# spb_sch1.net
KiCad netlist of a schematic drawn in Altium Designer
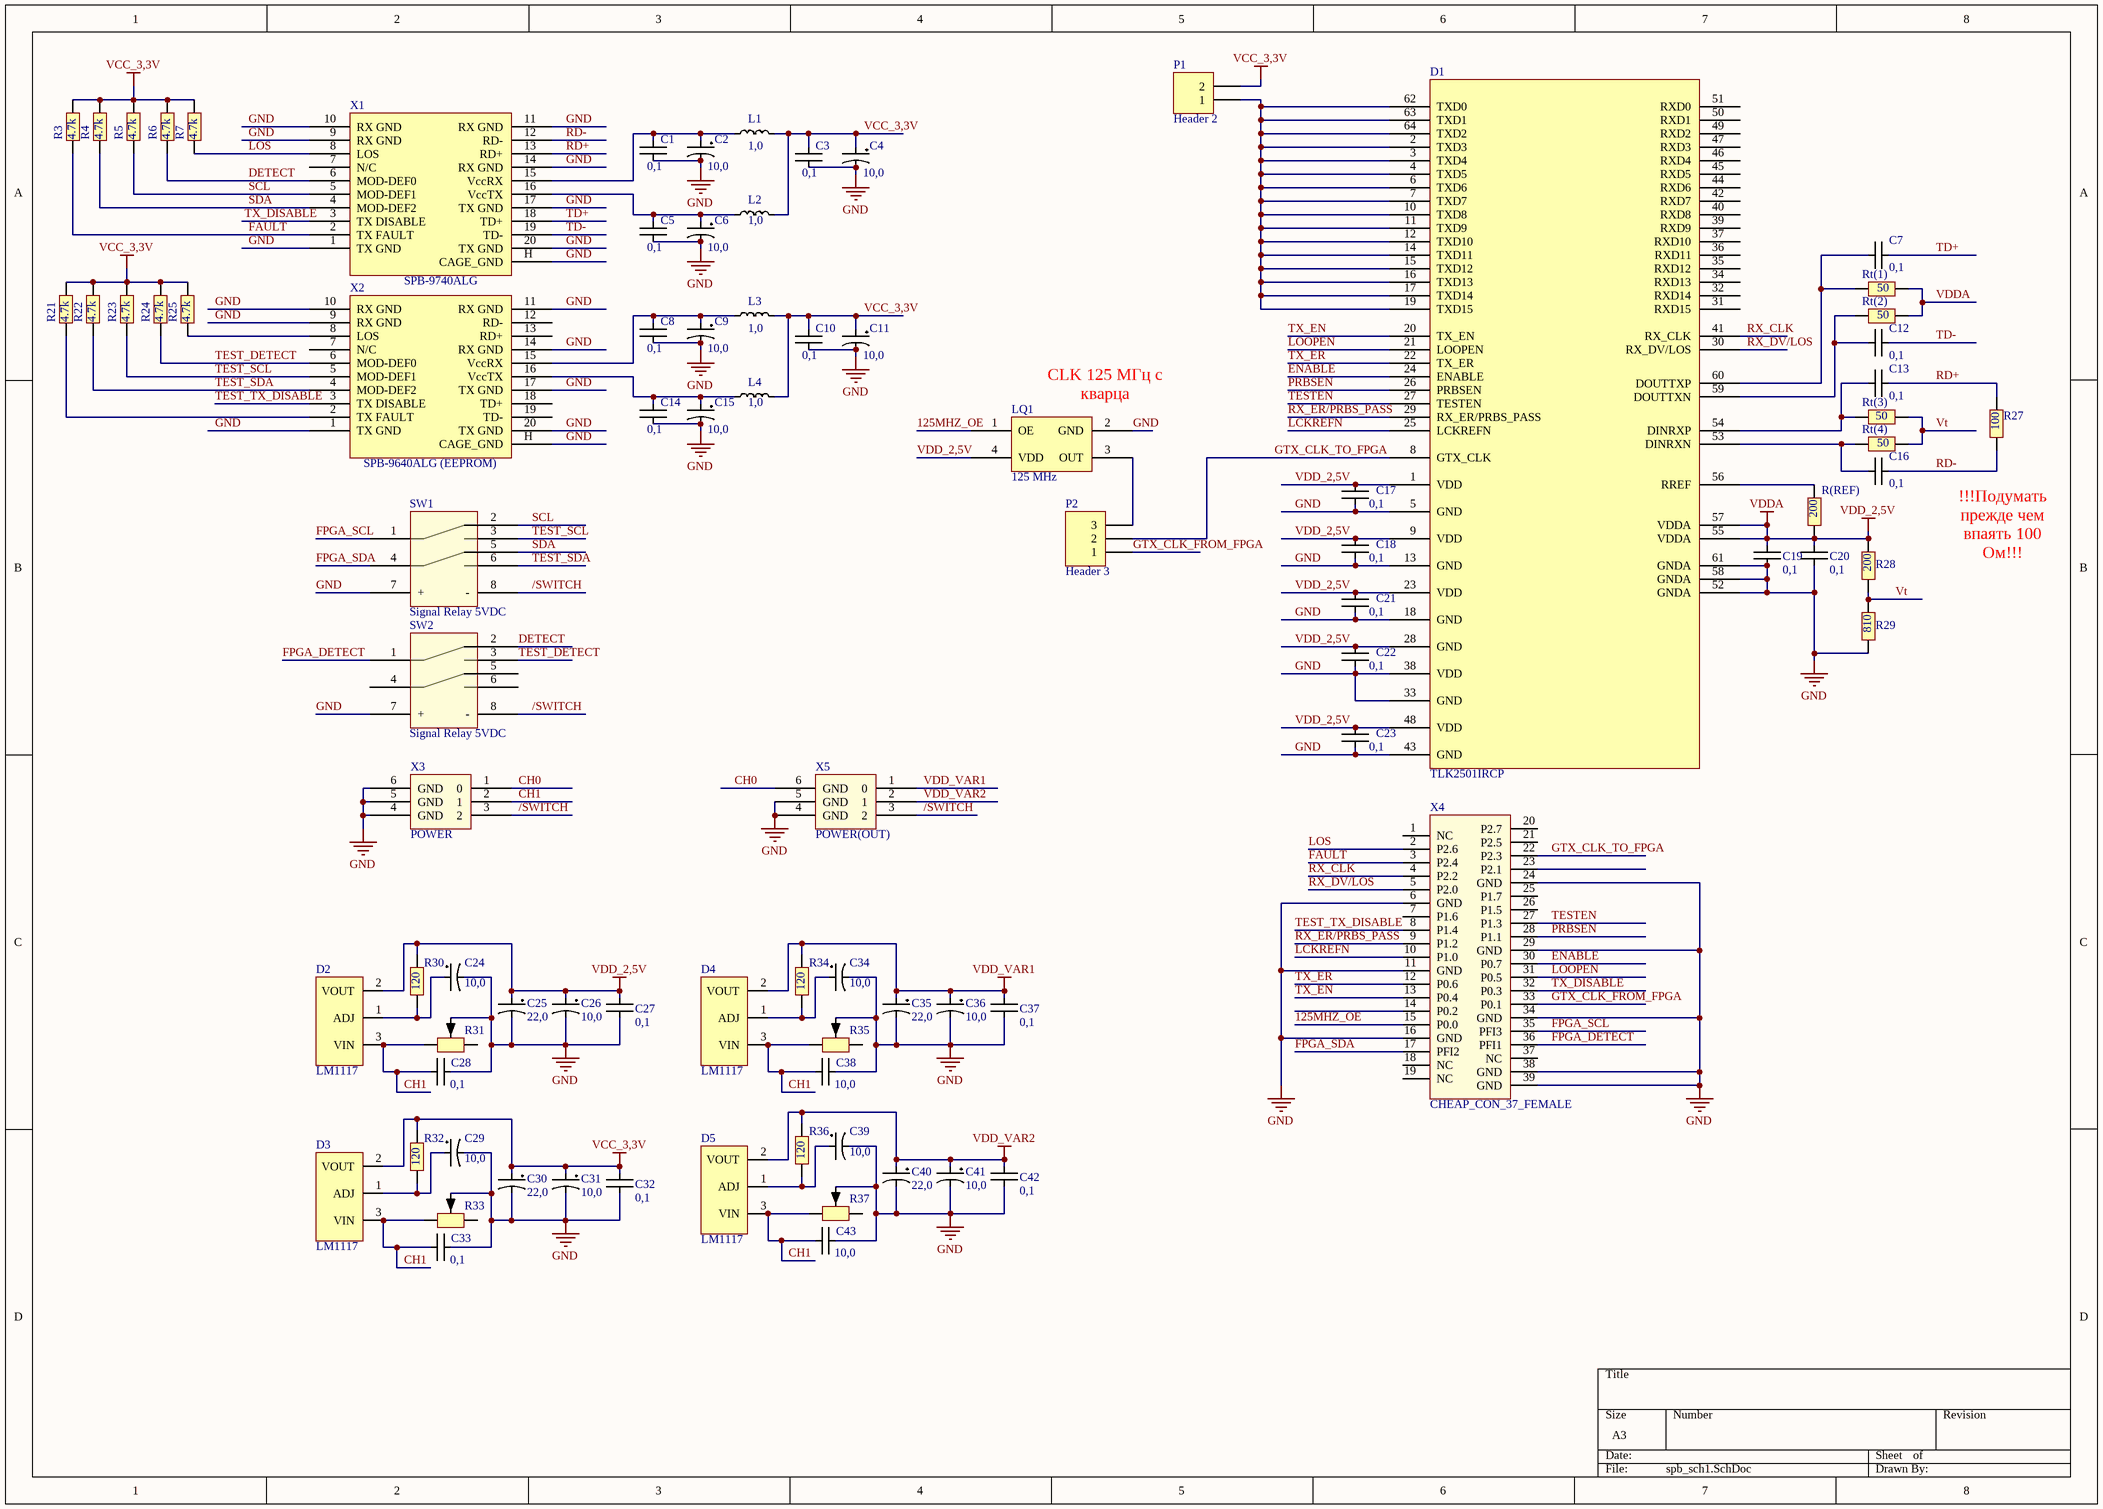
[diagram p0: spb_sch1.SchDoc]

(export (version "E")
  (design (tool "Eeschema 10.0.6"))
  (components
    (comp (ref "C1")
      (value "0,1")
      (footprint "0805")
      (description "0805")
      (libsource (lib "MIT_Schlib") (part "CAP_SMALL"))
    )
    (comp (ref "C2")
      (value "10,0")
      (footprint "TYPE_C")
      (description "SMD")
      (libsource (lib "MIT_Schlib") (part "CAP_TANT"))
    )
    (comp (ref "C3")
      (value "0,1")
      (footprint "0805")
      (description "0805")
      (libsource (lib "MIT_Schlib") (part "CAP_SMALL"))
    )
    (comp (ref "C4")
      (value "10,0")
      (footprint "TYPE_C")
      (description "SMD")
      (libsource (lib "MIT_Schlib") (part "CAP_TANT"))
    )
    (comp (ref "C5")
      (value "0,1")
      (footprint "0805")
      (description "0805")
      (libsource (lib "MIT_Schlib") (part "CAP_SMALL"))
    )
    (comp (ref "C6")
      (value "10,0")
      (footprint "TYPE_C")
      (description "SMD")
      (libsource (lib "MIT_Schlib") (part "CAP_TANT"))
    )
    (comp (ref "C7")
      (value "0,1")
      (footprint "0805")
      (description "0805")
      (libsource (lib "MIT_Schlib") (part "CAP_SMALL"))
    )
    (comp (ref "C8")
      (value "0,1")
      (footprint "0805")
      (description "0805")
      (libsource (lib "MIT_Schlib") (part "CAP_SMALL"))
    )
    (comp (ref "C9")
      (value "10,0")
      (footprint "TYPE_C")
      (description "SMD")
      (libsource (lib "MIT_Schlib") (part "CAP_TANT"))
    )
    (comp (ref "C10")
      (value "0,1")
      (footprint "0805")
      (description "0805")
      (libsource (lib "MIT_Schlib") (part "CAP_SMALL"))
    )
    (comp (ref "C11")
      (value "10,0")
      (footprint "TYPE_C")
      (description "SMD")
      (libsource (lib "MIT_Schlib") (part "CAP_TANT"))
    )
    (comp (ref "C12")
      (value "0,1")
      (footprint "0805")
      (description "0805")
      (libsource (lib "MIT_Schlib") (part "CAP_SMALL"))
    )
    (comp (ref "C13")
      (value "0,1")
      (footprint "0805")
      (description "0805")
      (libsource (lib "MIT_Schlib") (part "CAP_SMALL"))
    )
    (comp (ref "C14")
      (value "0,1")
      (footprint "0805")
      (description "0805")
      (libsource (lib "MIT_Schlib") (part "CAP_SMALL"))
    )
    (comp (ref "C15")
      (value "10,0")
      (footprint "TYPE_C")
      (description "SMD")
      (libsource (lib "MIT_Schlib") (part "CAP_TANT"))
    )
    (comp (ref "C16")
      (value "0,1")
      (footprint "0805")
      (description "0805")
      (libsource (lib "MIT_Schlib") (part "CAP_SMALL"))
    )
    (comp (ref "C17")
      (value "0,1")
      (footprint "0805")
      (description "0805")
      (libsource (lib "MIT_Schlib") (part "CAP_SMALL"))
    )
    (comp (ref "C18")
      (value "0,1")
      (footprint "0805")
      (description "0805")
      (libsource (lib "MIT_Schlib") (part "CAP_SMALL"))
    )
    (comp (ref "C19")
      (value "0,1")
      (footprint "0805")
      (description "0805")
      (libsource (lib "MIT_Schlib") (part "CAP_SMALL"))
    )
    (comp (ref "C20")
      (value "0,1")
      (footprint "0805")
      (description "0805")
      (libsource (lib "MIT_Schlib") (part "CAP_SMALL"))
    )
    (comp (ref "C21")
      (value "0,1")
      (footprint "0805")
      (description "0805")
      (libsource (lib "MIT_Schlib") (part "CAP_SMALL"))
    )
    (comp (ref "C22")
      (value "0,1")
      (footprint "0805")
      (description "0805")
      (libsource (lib "MIT_Schlib") (part "CAP_SMALL"))
    )
    (comp (ref "C23")
      (value "0,1")
      (footprint "0805")
      (description "0805")
      (libsource (lib "MIT_Schlib") (part "CAP_SMALL"))
    )
    (comp (ref "C24")
      (value "10,0")
      (footprint "TYPE_C")
      (description "SMD")
      (libsource (lib "MIT_Schlib") (part "CAP_TANT"))
    )
    (comp (ref "C25")
      (value "22,0")
      (footprint "TYPE_C")
      (description "SMD")
      (libsource (lib "MIT_Schlib") (part "CAP_TANT"))
    )
    (comp (ref "C26")
      (value "10,0")
      (footprint "TYPE_C")
      (description "SMD")
      (libsource (lib "MIT_Schlib") (part "CAP_TANT"))
    )
    (comp (ref "C27")
      (value "0,1")
      (footprint "0805")
      (description "0805")
      (libsource (lib "MIT_Schlib") (part "CAP_SMALL"))
    )
    (comp (ref "C28")
      (value "0,1")
      (footprint "0805")
      (description "0805")
      (libsource (lib "MIT_Schlib") (part "CAP_SMALL"))
    )
    (comp (ref "C29")
      (value "10,0")
      (footprint "TYPE_C")
      (description "SMD")
      (libsource (lib "MIT_Schlib") (part "CAP_TANT"))
    )
    (comp (ref "C30")
      (value "22,0")
      (footprint "TYPE_C")
      (description "SMD")
      (libsource (lib "MIT_Schlib") (part "CAP_TANT"))
    )
    (comp (ref "C31")
      (value "10,0")
      (footprint "TYPE_C")
      (description "SMD")
      (libsource (lib "MIT_Schlib") (part "CAP_TANT"))
    )
    (comp (ref "C32")
      (value "0,1")
      (footprint "0805")
      (description "0805")
      (libsource (lib "MIT_Schlib") (part "CAP_SMALL"))
    )
    (comp (ref "C33")
      (value "0,1")
      (footprint "0805")
      (description "0805")
      (libsource (lib "MIT_Schlib") (part "CAP_SMALL"))
    )
    (comp (ref "C34")
      (value "10,0")
      (footprint "TYPE_C")
      (description "SMD")
      (libsource (lib "MIT_Schlib") (part "CAP_TANT"))
    )
    (comp (ref "C35")
      (value "22,0")
      (footprint "TYPE_C")
      (description "SMD")
      (libsource (lib "MIT_Schlib") (part "CAP_TANT"))
    )
    (comp (ref "C36")
      (value "10,0")
      (footprint "TYPE_C")
      (description "SMD")
      (libsource (lib "MIT_Schlib") (part "CAP_TANT"))
    )
    (comp (ref "C37")
      (value "0,1")
      (footprint "0805")
      (description "0805")
      (libsource (lib "MIT_Schlib") (part "CAP_SMALL"))
    )
    (comp (ref "C38")
      (value "10,0")
      (footprint "0805")
      (description "0805")
      (libsource (lib "MIT_Schlib") (part "CAP_SMALL"))
    )
    (comp (ref "C39")
      (value "10,0")
      (footprint "TYPE_C")
      (description "SMD")
      (libsource (lib "MIT_Schlib") (part "CAP_TANT"))
    )
    (comp (ref "C40")
      (value "22,0")
      (footprint "TYPE_C")
      (description "SMD")
      (libsource (lib "MIT_Schlib") (part "CAP_TANT"))
    )
    (comp (ref "C41")
      (value "10,0")
      (footprint "TYPE_C")
      (description "SMD")
      (libsource (lib "MIT_Schlib") (part "CAP_TANT"))
    )
    (comp (ref "C42")
      (value "0,1")
      (footprint "0805")
      (description "0805")
      (libsource (lib "MIT_Schlib") (part "CAP_SMALL"))
    )
    (comp (ref "C43")
      (value "10,0")
      (footprint "0805")
      (description "0805")
      (libsource (lib "MIT_Schlib") (part "CAP_SMALL"))
    )
    (comp (ref "D1")
      (value "TLK2501IRCP")
      (footprint "Quad64")
      (libsource (lib "MIT_Schlib") (part "TLK2501IRCP"))
    )
    (comp (ref "D2") (value "LM1117") (footprint "TO-252") (libsource (lib "MIT_Schlib") (part "LM1117_ADJ")))
    (comp (ref "D3") (value "LM1117") (footprint "TO-252") (libsource (lib "MIT_Schlib") (part "LM1117_ADJ")))
    (comp (ref "D4") (value "LM1117") (footprint "TO-252") (libsource (lib "MIT_Schlib") (part "LM1117_ADJ")))
    (comp (ref "D5") (value "LM1117") (footprint "TO-252") (libsource (lib "MIT_Schlib") (part "LM1117_ADJ")))
    (comp (ref "L1")
      (value "1,0")
      (footprint "0805")
      (description "0805")
      (libsource (lib "MIT_Schlib") (part "INDUCT"))
    )
    (comp (ref "L2")
      (value "1,0")
      (footprint "0805")
      (description "0805")
      (libsource (lib "MIT_Schlib") (part "INDUCT"))
    )
    (comp (ref "L3")
      (value "1,0")
      (footprint "0805")
      (description "0805")
      (libsource (lib "MIT_Schlib") (part "INDUCT"))
    )
    (comp (ref "L4")
      (value "1,0")
      (footprint "0805")
      (description "0805")
      (libsource (lib "MIT_Schlib") (part "INDUCT"))
    )
    (comp (ref "LQ1")
      (value "125 MHz")
      (footprint "SOC7 SMD Clock Oscillator")
      (libsource (lib "MIT_Schlib") (part "SOC7 SMD Clock Oscillator"))
    )
    (comp (ref "P1")
      (value "Header 2")
      (footprint "HDR1X2")
      (description "Header, 2-Pin")
      (fields (field (name "PUBLISHER") "Altium Limited"))
      (libsource (lib "Miscellaneous Connectors") (part "Header 2"))
    )
    (comp (ref "P2")
      (value "Header 3")
      (footprint "HDR1X3")
      (description "Header, 3-Pin")
      (fields (field (name "PUBLISHER") "Altium Limited"))
      (libsource (lib "Miscellaneous Connectors") (part "Header 3"))
    )
    (comp (ref "R(REF)")
      (value "200")
      (footprint "0805")
      (description "0805")
      (libsource (lib "") (part "RES0805_1"))
    )
    (comp (ref "R3")
      (value "4.7k")
      (footprint "0805")
      (description "0805")
      (libsource (lib "") (part "RES0805_2"))
    )
    (comp (ref "R4")
      (value "4.7k")
      (footprint "0805")
      (description "0805")
      (libsource (lib "") (part "RES0805_2"))
    )
    (comp (ref "R5")
      (value "4.7k")
      (footprint "0805")
      (description "0805")
      (libsource (lib "") (part "RES0805_2"))
    )
    (comp (ref "R6")
      (value "4.7k")
      (footprint "0805")
      (description "0805")
      (libsource (lib "") (part "RES0805_2"))
    )
    (comp (ref "R7")
      (value "4.7k")
      (footprint "0805")
      (description "0805")
      (libsource (lib "") (part "RES0805_2"))
    )
    (comp (ref "R21")
      (value "4.7k")
      (footprint "0805")
      (description "0805")
      (libsource (lib "") (part "RES0805_2"))
    )
    (comp (ref "R22")
      (value "4.7k")
      (footprint "0805")
      (description "0805")
      (libsource (lib "") (part "RES0805_2"))
    )
    (comp (ref "R23")
      (value "4.7k")
      (footprint "0805")
      (description "0805")
      (libsource (lib "") (part "RES0805_2"))
    )
    (comp (ref "R24")
      (value "4.7k")
      (footprint "0805")
      (description "0805")
      (libsource (lib "") (part "RES0805_2"))
    )
    (comp (ref "R25")
      (value "4.7k")
      (footprint "0805")
      (description "0805")
      (libsource (lib "") (part "RES0805_2"))
    )
    (comp (ref "R27")
      (value "100")
      (footprint "0805")
      (description "0805")
      (libsource (lib "") (part "RES0805_2"))
    )
    (comp (ref "R28")
      (value "200")
      (footprint "0805")
      (description "0805")
      (libsource (lib "") (part "RES0805_1"))
    )
    (comp (ref "R29")
      (value "810")
      (footprint "0805")
      (description "0805")
      (libsource (lib "") (part "RES0805_1"))
    )
    (comp (ref "R30")
      (value "120")
      (footprint "0805")
      (description "0805")
      (libsource (lib "") (part "RES0805_2"))
    )
    (comp (ref "R31")
      (value "RES_VAR")
      (footprint "3006P")
      (description "PV36W102C (СП5-2ВБ) 1 кОм")
      (libsource (lib "MIT_Schlib") (part "RES_VAR"))
    )
    (comp (ref "R32") (value "120") (footprint "0805") (libsource (lib "") (part "RES0805_2")))
    (comp (ref "R33")
      (value "RES_VAR")
      (footprint "3006P")
      (description "PV36W102C (СП5-2ВБ) 1 кОм")
      (libsource (lib "MIT_Schlib") (part "RES_VAR"))
    )
    (comp (ref "R34")
      (value "120")
      (footprint "0805")
      (description "0805")
      (libsource (lib "") (part "RES0805_2"))
    )
    (comp (ref "R35")
      (value "RES_VAR")
      (footprint "3006P")
      (description "PV36W102C (СП5-2ВБ) 1 кОм")
      (libsource (lib "MIT_Schlib") (part "RES_VAR"))
    )
    (comp (ref "R36")
      (value "120")
      (footprint "0805")
      (description "0805")
      (libsource (lib "") (part "RES0805_2"))
    )
    (comp (ref "R37")
      (value "RES_VAR")
      (footprint "3006P")
      (description "PV36W102C (СП5-2ВБ) 1 кОм")
      (libsource (lib "MIT_Schlib") (part "RES_VAR"))
    )
    (comp (ref "Rt(1)")
      (value "50")
      (footprint "0805")
      (description "0805")
      (libsource (lib "MIT_Schlib") (part "RES0805"))
    )
    (comp (ref "Rt(2)")
      (value "50")
      (footprint "0805")
      (description "0805")
      (libsource (lib "MIT_Schlib") (part "RES0805"))
    )
    (comp (ref "Rt(3)")
      (value "50")
      (footprint "0805")
      (description "0805")
      (libsource (lib "MIT_Schlib") (part "RES0805"))
    )
    (comp (ref "Rt(4)")
      (value "50")
      (footprint "0805")
      (description "0805")
      (libsource (lib "MIT_Schlib") (part "RES0805"))
    )
    (comp (ref "SW1")
      (value "Signal Relay 5VDC")
      (footprint "V23079 Relay")
      (libsource (lib "MIT_Schlib") (part "SWITCH"))
    )
    (comp (ref "SW2")
      (value "Signal Relay 5VDC")
      (footprint "V23079 Relay")
      (libsource (lib "MIT_Schlib") (part "SWITCH"))
    )
    (comp (ref "X1")
      (value "SPB-9740ALG")
      (footprint "SFP-20pin")
      (libsource (lib "MIT_Schlib") (part "SFP-20pin"))
    )
    (comp (ref "X2")
      (value "SPB-9640ALG (EEPROM)")
      (footprint "SFP-20pin")
      (libsource (lib "MIT_Schlib") (part "SFP-20pin"))
    )
    (comp (ref "X3") (value "POWER") (footprint "POWER") (libsource (lib "Schlib") (part "POWER")))
    (comp (ref "X4")
      (value "CHEAP_CON_37_FEMALE")
      (footprint "CHEAP_CONN_FEMALE")
      (libsource (lib "Schlib") (part "CHEAP_CON_37_FEMALE"))
    )
    (comp (ref "X5") (value "POWER(OUT)") (footprint "POWER") (libsource (lib "Schlib") (part "POWER")))
  )
  (nets
    (net (code "1") (name "/125MHZ_OE") (class "Default")
      (node (ref "LQ1") (pin "1") (pinfunction "OE_1") (pintype "passive"))
      (node (ref "X4") (pin "15") (pinfunction "P0.0_15") (pintype "passive"))
    )
    (net (code "3") (name "/CH0") (class "Default")
      (node (ref "X3") (pin "1") (pinfunction "0_1") (pintype "passive"))
      (node (ref "X5") (pin "6") (pinfunction "GND_6") (pintype "passive"))
    )
    (net (code "4") (name "/CH1") (class "Default")
      (node (ref "C28") (pin "1") (pinfunction "1_1") (pintype "passive"))
      (node (ref "C33") (pin "1") (pinfunction "1_1") (pintype "passive"))
      (node (ref "C38") (pin "1") (pinfunction "1_1") (pintype "passive"))
      (node (ref "C43") (pin "1") (pinfunction "1_1") (pintype "passive"))
      (node (ref "D2") (pin "3") (pinfunction "VIN_3") (pintype "passive"))
      (node (ref "D3") (pin "3") (pinfunction "VIN_3") (pintype "passive"))
      (node (ref "D4") (pin "3") (pinfunction "VIN_3") (pintype "passive"))
      (node (ref "D5") (pin "3") (pinfunction "VIN_3") (pintype "passive"))
      (node (ref "R31") (pin "3") (pinfunction "3_3") (pintype "passive"))
      (node (ref "R33") (pin "3") (pinfunction "3_3") (pintype "passive"))
      (node (ref "R35") (pin "3") (pinfunction "3_3") (pintype "passive"))
      (node (ref "R37") (pin "3") (pinfunction "3_3") (pintype "passive"))
      (node (ref "X3") (pin "2") (pinfunction "1_2") (pintype "passive"))
    )
    (net (code "5") (name "/DETECT") (class "Default")
      (node (ref "R6") (pin "2") (pinfunction "2_2") (pintype "passive"))
      (node (ref "SW2") (pin "2") (pinfunction "-_2") (pintype "passive"))
      (node (ref "X1") (pin "6") (pinfunction "MOD-DEF0_6") (pintype "passive"))
    )
    (net (code "6") (name "/ENABLE") (class "Default")
      (node (ref "D1") (pin "24") (pinfunction "ENABLE_24") (pintype "passive"))
      (node (ref "X4") (pin "30") (pinfunction "P0.7_30") (pintype "passive"))
    )
    (net (code "7") (name "/FAULT") (class "Default")
      (node (ref "R3") (pin "2") (pinfunction "2_2") (pintype "passive"))
      (node (ref "X1") (pin "2") (pinfunction "TX_FAULT_2") (pintype "passive"))
      (node (ref "X4") (pin "3") (pinfunction "P2.4_3") (pintype "passive"))
    )
    (net (code "8") (name "/FPGA_DETECT") (class "Default")
      (node (ref "SW2") (pin "1") (pinfunction "-_1") (pintype "passive"))
      (node (ref "X4") (pin "36") (pinfunction "PFI1_36") (pintype "passive"))
    )
    (net (code "9") (name "/FPGA_SCL") (class "Default")
      (node (ref "SW1") (pin "1") (pinfunction "-_1") (pintype "passive"))
      (node (ref "X4") (pin "35") (pinfunction "PFI3_35") (pintype "passive"))
    )
    (net (code "10") (name "/FPGA_SDA") (class "Default")
      (node (ref "SW1") (pin "4") (pinfunction "-_4") (pintype "passive"))
      (node (ref "X4") (pin "17") (pinfunction "PFI2_17") (pintype "passive"))
    )
    (net (code "11") (name "/GTX_CLK_FROM_FPGA") (class "Default")
      (node (ref "P2") (pin "1") (pinfunction "1_1") (pintype "passive"))
      (node (ref "X4") (pin "33") (pinfunction "P0.1_33") (pintype "passive"))
    )
    (net (code "12") (name "/GTX_CLK_TO_FPGA") (class "Default")
      (node (ref "D1") (pin "8") (pinfunction "GTX_CLK_8") (pintype "passive"))
      (node (ref "P2") (pin "2") (pinfunction "2_2") (pintype "passive"))
      (node (ref "X4") (pin "22") (pinfunction "P2.3_22") (pintype "passive"))
    )
    (net (code "13") (name "/LCKREFN") (class "Default")
      (node (ref "D1") (pin "25") (pinfunction "LCKREFN_25") (pintype "passive"))
      (node (ref "X4") (pin "10") (pinfunction "P1.0_10") (pintype "passive"))
    )
    (net (code "14") (name "/LOOPEN") (class "Default")
      (node (ref "D1") (pin "21") (pinfunction "LOOPEN_21") (pintype "passive"))
      (node (ref "X4") (pin "31") (pinfunction "P0.5_31") (pintype "passive"))
    )
    (net (code "15") (name "/LOS") (class "Default")
      (node (ref "R7") (pin "2") (pinfunction "2_2") (pintype "passive"))
      (node (ref "X1") (pin "8") (pinfunction "LOS_8") (pintype "passive"))
      (node (ref "X4") (pin "2") (pinfunction "P2.6_2") (pintype "passive"))
    )
    (net (code "16") (name "/PRBSEN") (class "Default")
      (node (ref "D1") (pin "26") (pinfunction "PRBSEN_26") (pintype "passive"))
      (node (ref "X4") (pin "28") (pinfunction "P1.1_28") (pintype "passive"))
    )
    (net (code "17") (name "/RD+") (class "Default")
      (node (ref "C13") (pin "1") (pinfunction "1_1") (pintype "passive"))
      (node (ref "R27") (pin "1") (pinfunction "1_1") (pintype "passive"))
      (node (ref "X1") (pin "13") (pinfunction "RD+_13") (pintype "passive"))
    )
    (net (code "18") (name "/RD-") (class "Default")
      (node (ref "C16") (pin "1") (pinfunction "1_1") (pintype "passive"))
      (node (ref "R27") (pin "2") (pinfunction "2_2") (pintype "passive"))
      (node (ref "X1") (pin "12") (pinfunction "RD-_12") (pintype "passive"))
    )
    (net (code "19") (name "/RX_CLK") (class "Default")
      (node (ref "D1") (pin "41") (pinfunction "RX_CLK_41") (pintype "passive"))
      (node (ref "X4") (pin "4") (pinfunction "P2.2_4") (pintype "passive"))
    )
    (net (code "20") (name "/RX_DV{slash}LOS") (class "Default")
      (node (ref "D1") (pin "30") (pinfunction "RX_DV/LOS_30") (pintype "passive"))
      (node (ref "X4") (pin "5") (pinfunction "P2.0_5") (pintype "passive"))
    )
    (net (code "21") (name "/RX_ER{slash}PRBS_PASS") (class "Default")
      (node (ref "D1") (pin "29") (pinfunction "RX_ER/PRBS_PASS_29") (pintype "passive"))
      (node (ref "X4") (pin "9") (pinfunction "P1.2_9") (pintype "passive"))
    )
    (net (code "22") (name "/SCL") (class "Default")
      (node (ref "R5") (pin "2") (pinfunction "2_2") (pintype "passive"))
      (node (ref "SW1") (pin "2") (pinfunction "-_2") (pintype "passive"))
      (node (ref "X1") (pin "5") (pinfunction "MOD-DEF1_5") (pintype "passive"))
    )
    (net (code "23") (name "/SDA") (class "Default")
      (node (ref "R4") (pin "2") (pinfunction "2_2") (pintype "passive"))
      (node (ref "SW1") (pin "5") (pinfunction "-_5") (pintype "passive"))
      (node (ref "X1") (pin "4") (pinfunction "MOD-DEF2_4") (pintype "passive"))
    )
    (net (code "24") (name "/TD+") (class "Default")
      (node (ref "C7") (pin "1") (pinfunction "1_1") (pintype "passive"))
      (node (ref "X1") (pin "18") (pinfunction "TD+_18") (pintype "passive"))
    )
    (net (code "25") (name "/TD-") (class "Default")
      (node (ref "C12") (pin "1") (pinfunction "1_1") (pintype "passive"))
      (node (ref "X1") (pin "19") (pinfunction "TD-_19") (pintype "passive"))
    )
    (net (code "26") (name "/TESTEN") (class "Default")
      (node (ref "D1") (pin "27") (pinfunction "TESTEN_27") (pintype "passive"))
      (node (ref "X4") (pin "27") (pinfunction "P1.3_27") (pintype "passive"))
    )
    (net (code "27") (name "/TEST_DETECT") (class "Default")
      (node (ref "R24") (pin "2") (pinfunction "2_2") (pintype "passive"))
      (node (ref "SW2") (pin "3") (pinfunction "-_3") (pintype "passive"))
      (node (ref "X2") (pin "6") (pinfunction "MOD-DEF0_6") (pintype "passive"))
    )
    (net (code "28") (name "/TEST_SCL") (class "Default")
      (node (ref "R23") (pin "2") (pinfunction "2_2") (pintype "passive"))
      (node (ref "SW1") (pin "3") (pinfunction "-_3") (pintype "passive"))
      (node (ref "X2") (pin "5") (pinfunction "MOD-DEF1_5") (pintype "passive"))
    )
    (net (code "29") (name "/TEST_SDA") (class "Default")
      (node (ref "R22") (pin "2") (pinfunction "2_2") (pintype "passive"))
      (node (ref "SW1") (pin "6") (pinfunction "-_6") (pintype "passive"))
      (node (ref "X2") (pin "4") (pinfunction "MOD-DEF2_4") (pintype "passive"))
    )
    (net (code "30") (name "/TEST_TX_DISABLE") (class "Default")
      (node (ref "X2") (pin "3") (pinfunction "TX_DISABLE_3") (pintype "passive"))
      (node (ref "X4") (pin "8") (pinfunction "P1.4_8") (pintype "passive"))
    )
    (net (code "31") (name "/TX_DISABLE") (class "Default")
      (node (ref "X1") (pin "3") (pinfunction "TX_DISABLE_3") (pintype "passive"))
      (node (ref "X4") (pin "32") (pinfunction "P0.3_32") (pintype "passive"))
    )
    (net (code "32") (name "/TX_EN") (class "Default")
      (node (ref "D1") (pin "20") (pinfunction "TX_EN_20") (pintype "passive"))
      (node (ref "X4") (pin "13") (pinfunction "P0.4_13") (pintype "passive"))
    )
    (net (code "33") (name "/TX_ER") (class "Default")
      (node (ref "D1") (pin "22") (pinfunction "TX_ER_22") (pintype "passive"))
      (node (ref "X4") (pin "12") (pinfunction "P0.6_12") (pintype "passive"))
    )
    (net (code "34") (name "/Vt") (class "Default")
      (node (ref "R28") (pin "1") (pinfunction "1_1") (pintype "passive"))
      (node (ref "R29") (pin "2") (pinfunction "2_2") (pintype "passive"))
      (node (ref "Rt(3)") (pin "1") (pinfunction "1_1") (pintype "passive"))
      (node (ref "Rt(4)") (pin "1") (pinfunction "1_1") (pintype "passive"))
    )
    (net (code "35") (name "/{slash}SWITCH") (class "Default")
      (node (ref "SW1") (pin "8") (pinfunction "-_8") (pintype "passive"))
      (node (ref "SW2") (pin "8") (pinfunction "-_8") (pintype "passive"))
      (node (ref "X3") (pin "3") (pinfunction "2_3") (pintype "passive"))
      (node (ref "X5") (pin "3") (pinfunction "2_3") (pintype "passive"))
    )
    (net (code "36") (name "GND") (class "Default")
      (node (ref "C1") (pin "2") (pinfunction "2_2") (pintype "passive"))
      (node (ref "C10") (pin "2") (pinfunction "2_2") (pintype "passive"))
      (node (ref "C11") (pin "1") (pinfunction "1_1") (pintype "passive"))
      (node (ref "C14") (pin "2") (pinfunction "2_2") (pintype "passive"))
      (node (ref "C15") (pin "1") (pinfunction "1_1") (pintype "passive"))
      (node (ref "C17") (pin "2") (pinfunction "2_2") (pintype "passive"))
      (node (ref "C18") (pin "2") (pinfunction "2_2") (pintype "passive"))
      (node (ref "C19") (pin "1") (pinfunction "1_1") (pintype "passive"))
      (node (ref "C2") (pin "1") (pinfunction "1_1") (pintype "passive"))
      (node (ref "C20") (pin "1") (pinfunction "1_1") (pintype "passive"))
      (node (ref "C21") (pin "2") (pinfunction "2_2") (pintype "passive"))
      (node (ref "C22") (pin "2") (pinfunction "2_2") (pintype "passive"))
      (node (ref "C23") (pin "2") (pinfunction "2_2") (pintype "passive"))
      (node (ref "C24") (pin "1") (pinfunction "1_1") (pintype "passive"))
      (node (ref "C25") (pin "1") (pinfunction "1_1") (pintype "passive"))
      (node (ref "C26") (pin "1") (pinfunction "1_1") (pintype "passive"))
      (node (ref "C27") (pin "1") (pinfunction "1_1") (pintype "passive"))
      (node (ref "C28") (pin "2") (pinfunction "2_2") (pintype "passive"))
      (node (ref "C29") (pin "1") (pinfunction "1_1") (pintype "passive"))
      (node (ref "C3") (pin "2") (pinfunction "2_2") (pintype "passive"))
      (node (ref "C30") (pin "1") (pinfunction "1_1") (pintype "passive"))
      (node (ref "C31") (pin "1") (pinfunction "1_1") (pintype "passive"))
      (node (ref "C32") (pin "1") (pinfunction "1_1") (pintype "passive"))
      (node (ref "C33") (pin "2") (pinfunction "2_2") (pintype "passive"))
      (node (ref "C34") (pin "1") (pinfunction "1_1") (pintype "passive"))
      (node (ref "C35") (pin "1") (pinfunction "1_1") (pintype "passive"))
      (node (ref "C36") (pin "1") (pinfunction "1_1") (pintype "passive"))
      (node (ref "C37") (pin "1") (pinfunction "1_1") (pintype "passive"))
      (node (ref "C38") (pin "2") (pinfunction "2_2") (pintype "passive"))
      (node (ref "C39") (pin "1") (pinfunction "1_1") (pintype "passive"))
      (node (ref "C4") (pin "1") (pinfunction "1_1") (pintype "passive"))
      (node (ref "C40") (pin "1") (pinfunction "1_1") (pintype "passive"))
      (node (ref "C41") (pin "1") (pinfunction "1_1") (pintype "passive"))
      (node (ref "C42") (pin "1") (pinfunction "1_1") (pintype "passive"))
      (node (ref "C43") (pin "2") (pinfunction "2_2") (pintype "passive"))
      (node (ref "C5") (pin "2") (pinfunction "2_2") (pintype "passive"))
      (node (ref "C6") (pin "1") (pinfunction "1_1") (pintype "passive"))
      (node (ref "C8") (pin "2") (pinfunction "2_2") (pintype "passive"))
      (node (ref "C9") (pin "1") (pinfunction "1_1") (pintype "passive"))
      (node (ref "D1") (pin "13") (pinfunction "GND_13") (pintype "passive"))
      (node (ref "D1") (pin "18") (pinfunction "GND_18") (pintype "passive"))
      (node (ref "D1") (pin "33") (pinfunction "GND_33") (pintype "passive"))
      (node (ref "D1") (pin "38") (pinfunction "VDD_38") (pintype "passive"))
      (node (ref "D1") (pin "43") (pinfunction "GND_43") (pintype "passive"))
      (node (ref "D1") (pin "5") (pinfunction "GND_5") (pintype "passive"))
      (node (ref "D1") (pin "52") (pinfunction "GNDA_52") (pintype "passive"))
      (node (ref "D1") (pin "58") (pinfunction "GNDA_58") (pintype "passive"))
      (node (ref "D1") (pin "61") (pinfunction "GNDA_61") (pintype "passive"))
      (node (ref "LQ1") (pin "2") (pinfunction "GND_2") (pintype "passive"))
      (node (ref "R29") (pin "1") (pinfunction "1_1") (pintype "passive"))
      (node (ref "R31") (pin "2") (pinfunction "2_2") (pintype "passive"))
      (node (ref "R33") (pin "2") (pinfunction "2_2") (pintype "passive"))
      (node (ref "R35") (pin "2") (pinfunction "2_2") (pintype "passive"))
      (node (ref "R37") (pin "2") (pinfunction "2_2") (pintype "passive"))
      (node (ref "SW1") (pin "7") (pinfunction "+_7") (pintype "passive"))
      (node (ref "SW2") (pin "7") (pinfunction "+_7") (pintype "passive"))
      (node (ref "X1") (pin "1") (pinfunction "TX_GND_1") (pintype "passive"))
      (node (ref "X1") (pin "10") (pinfunction "RX_GND_10") (pintype "passive"))
      (node (ref "X1") (pin "11") (pinfunction "RX_GND_11") (pintype "passive"))
      (node (ref "X1") (pin "14") (pinfunction "RX_GND_14") (pintype "passive"))
      (node (ref "X1") (pin "17") (pinfunction "TX_GND_17") (pintype "passive"))
      (node (ref "X1") (pin "20") (pinfunction "TX_GND_20") (pintype "passive"))
      (node (ref "X1") (pin "9") (pinfunction "RX_GND_9") (pintype "passive"))
      (node (ref "X1") (pin "H") (pinfunction "CAGE_GND_H") (pintype "passive"))
      (node (ref "X2") (pin "1") (pinfunction "TX_GND_1") (pintype "passive"))
      (node (ref "X2") (pin "10") (pinfunction "RX_GND_10") (pintype "passive"))
      (node (ref "X2") (pin "11") (pinfunction "RX_GND_11") (pintype "passive"))
      (node (ref "X2") (pin "14") (pinfunction "RX_GND_14") (pintype "passive"))
      (node (ref "X2") (pin "17") (pinfunction "TX_GND_17") (pintype "passive"))
      (node (ref "X2") (pin "20") (pinfunction "TX_GND_20") (pintype "passive"))
      (node (ref "X2") (pin "9") (pinfunction "RX_GND_9") (pintype "passive"))
      (node (ref "X2") (pin "H") (pinfunction "CAGE_GND_H") (pintype "passive"))
      (node (ref "X3") (pin "4") (pinfunction "GND_4") (pintype "passive"))
      (node (ref "X3") (pin "5") (pinfunction "GND_5") (pintype "passive"))
      (node (ref "X3") (pin "6") (pinfunction "GND_6") (pintype "passive"))
      (node (ref "X4") (pin "11") (pinfunction "GND_11") (pintype "passive"))
      (node (ref "X4") (pin "16") (pinfunction "GND_16") (pintype "passive"))
      (node (ref "X4") (pin "24") (pinfunction "GND_24") (pintype "passive"))
      (node (ref "X4") (pin "29") (pinfunction "GND_29") (pintype "passive"))
      (node (ref "X4") (pin "34") (pinfunction "GND_34") (pintype "passive"))
      (node (ref "X4") (pin "38") (pinfunction "GND_38") (pintype "passive"))
      (node (ref "X4") (pin "39") (pinfunction "GND_39") (pintype "passive"))
      (node (ref "X4") (pin "6") (pinfunction "GND_6") (pintype "passive"))
      (node (ref "X5") (pin "4") (pinfunction "GND_4") (pintype "passive"))
      (node (ref "X5") (pin "5") (pinfunction "GND_5") (pintype "passive"))
    )
    (net (code "37") (name "Net-(D1-DINRXN)") (class "Default")
      (node (ref "C16") (pin "2") (pinfunction "2_2") (pintype "passive"))
      (node (ref "D1") (pin "53") (pinfunction "DINRXN_53") (pintype "passive"))
      (node (ref "Rt(4)") (pin "2") (pinfunction "2_2") (pintype "passive"))
    )
    (net (code "38") (name "Net-(D1-DINRXP)") (class "Default")
      (node (ref "C13") (pin "2") (pinfunction "2_2") (pintype "passive"))
      (node (ref "D1") (pin "54") (pinfunction "DINRXP_54") (pintype "passive"))
      (node (ref "Rt(3)") (pin "2") (pinfunction "2_2") (pintype "passive"))
    )
    (net (code "39") (name "Net-(D1-DOUTTXN)") (class "Default")
      (node (ref "C12") (pin "2") (pinfunction "2_2") (pintype "passive"))
      (node (ref "D1") (pin "59") (pinfunction "DOUTTXN_59") (pintype "passive"))
      (node (ref "Rt(2)") (pin "2") (pinfunction "2_2") (pintype "passive"))
    )
    (net (code "40") (name "Net-(D1-DOUTTXP)") (class "Default")
      (node (ref "C7") (pin "2") (pinfunction "2_2") (pintype "passive"))
      (node (ref "D1") (pin "60") (pinfunction "DOUTTXP_60") (pintype "passive"))
      (node (ref "Rt(1)") (pin "2") (pinfunction "2_2") (pintype "passive"))
    )
    (net (code "41") (name "Net-(D1-RREF)") (class "Default")
      (node (ref "D1") (pin "56") (pinfunction "RREF_56") (pintype "passive"))
      (node (ref "R(REF)") (pin "2") (pinfunction "2_2") (pintype "passive"))
    )
    (net (code "42") (name "Net-(D1-TXD0)") (class "Default")
      (node (ref "D1") (pin "10") (pinfunction "TXD8_10") (pintype "passive"))
      (node (ref "D1") (pin "11") (pinfunction "TXD9_11") (pintype "passive"))
      (node (ref "D1") (pin "12") (pinfunction "TXD10_12") (pintype "passive"))
      (node (ref "D1") (pin "14") (pinfunction "TXD11_14") (pintype "passive"))
      (node (ref "D1") (pin "15") (pinfunction "TXD12_15") (pintype "passive"))
      (node (ref "D1") (pin "16") (pinfunction "TXD13_16") (pintype "passive"))
      (node (ref "D1") (pin "17") (pinfunction "TXD14_17") (pintype "passive"))
      (node (ref "D1") (pin "19") (pinfunction "TXD15_19") (pintype "passive"))
      (node (ref "D1") (pin "2") (pinfunction "TXD3_2") (pintype "passive"))
      (node (ref "D1") (pin "3") (pinfunction "TXD4_3") (pintype "passive"))
      (node (ref "D1") (pin "4") (pinfunction "TXD5_4") (pintype "passive"))
      (node (ref "D1") (pin "6") (pinfunction "TXD6_6") (pintype "passive"))
      (node (ref "D1") (pin "62") (pinfunction "TXD0_62") (pintype "passive"))
      (node (ref "D1") (pin "63") (pinfunction "TXD1_63") (pintype "passive"))
      (node (ref "D1") (pin "64") (pinfunction "TXD2_64") (pintype "passive"))
      (node (ref "D1") (pin "7") (pinfunction "TXD7_7") (pintype "passive"))
      (node (ref "P1") (pin "1") (pinfunction "1_1") (pintype "passive"))
    )
    (net (code "43") (name "Net-(D2-ADJ)") (class "Default")
      (node (ref "C24") (pin "2") (pinfunction "2_2") (pintype "passive"))
      (node (ref "D2") (pin "1") (pinfunction "ADJ_1") (pintype "passive"))
      (node (ref "R30") (pin "2") (pinfunction "2_2") (pintype "passive"))
    )
    (net (code "44") (name "Net-(D3-ADJ)") (class "Default")
      (node (ref "C29") (pin "2") (pinfunction "2_2") (pintype "passive"))
      (node (ref "D3") (pin "1") (pinfunction "ADJ_1") (pintype "passive"))
      (node (ref "R32") (pin "2") (pinfunction "2_2") (pintype "passive"))
    )
    (net (code "45") (name "Net-(D4-ADJ)") (class "Default")
      (node (ref "C34") (pin "2") (pinfunction "2_2") (pintype "passive"))
      (node (ref "D4") (pin "1") (pinfunction "ADJ_1") (pintype "passive"))
      (node (ref "R34") (pin "2") (pinfunction "2_2") (pintype "passive"))
    )
    (net (code "46") (name "Net-(D5-ADJ)") (class "Default")
      (node (ref "C39") (pin "2") (pinfunction "2_2") (pintype "passive"))
      (node (ref "D5") (pin "1") (pinfunction "ADJ_1") (pintype "passive"))
      (node (ref "R36") (pin "2") (pinfunction "2_2") (pintype "passive"))
    )
    (net (code "47") (name "Net-(LQ1-OUT)") (class "Default")
      (node (ref "LQ1") (pin "3") (pinfunction "OUT_3") (pintype "passive"))
      (node (ref "P2") (pin "3") (pinfunction "3_3") (pintype "passive"))
    )
    (net (code "48") (name "Net-(X1-VccRX)") (class "Default")
      (node (ref "C1") (pin "1") (pinfunction "1_1") (pintype "passive"))
      (node (ref "C2") (pin "2") (pinfunction "2_2") (pintype "passive"))
      (node (ref "L1") (pin "1") (pinfunction "1_1") (pintype "passive"))
      (node (ref "X1") (pin "15") (pinfunction "VccRX_15") (pintype "passive"))
    )
    (net (code "49") (name "Net-(X1-VccTX)") (class "Default")
      (node (ref "C5") (pin "1") (pinfunction "1_1") (pintype "passive"))
      (node (ref "C6") (pin "2") (pinfunction "2_2") (pintype "passive"))
      (node (ref "L2") (pin "1") (pinfunction "1_1") (pintype "passive"))
      (node (ref "X1") (pin "16") (pinfunction "VccTX_16") (pintype "passive"))
    )
    (net (code "50") (name "Net-(X2-LOS)") (class "Default")
      (node (ref "R25") (pin "2") (pinfunction "2_2") (pintype "passive"))
      (node (ref "X2") (pin "8") (pinfunction "LOS_8") (pintype "passive"))
    )
    (net (code "51") (name "Net-(X2-TX_FAULT)") (class "Default")
      (node (ref "R21") (pin "2") (pinfunction "2_2") (pintype "passive"))
      (node (ref "X2") (pin "2") (pinfunction "TX_FAULT_2") (pintype "passive"))
    )
    (net (code "52") (name "Net-(X2-VccRX)") (class "Default")
      (node (ref "C8") (pin "1") (pinfunction "1_1") (pintype "passive"))
      (node (ref "C9") (pin "2") (pinfunction "2_2") (pintype "passive"))
      (node (ref "L3") (pin "1") (pinfunction "1_1") (pintype "passive"))
      (node (ref "X2") (pin "15") (pinfunction "VccRX_15") (pintype "passive"))
    )
    (net (code "53") (name "Net-(X2-VccTX)") (class "Default")
      (node (ref "C14") (pin "1") (pinfunction "1_1") (pintype "passive"))
      (node (ref "C15") (pin "2") (pinfunction "2_2") (pintype "passive"))
      (node (ref "L4") (pin "1") (pinfunction "1_1") (pintype "passive"))
      (node (ref "X2") (pin "16") (pinfunction "VccTX_16") (pintype "passive"))
    )
    (net (code "54") (name "VCC_3,3V") (class "Default")
      (node (ref "C10") (pin "1") (pinfunction "1_1") (pintype "passive"))
      (node (ref "C11") (pin "2") (pinfunction "2_2") (pintype "passive"))
      (node (ref "C3") (pin "1") (pinfunction "1_1") (pintype "passive"))
      (node (ref "C30") (pin "2") (pinfunction "2_2") (pintype "passive"))
      (node (ref "C31") (pin "2") (pinfunction "2_2") (pintype "passive"))
      (node (ref "C32") (pin "2") (pinfunction "2_2") (pintype "passive"))
      (node (ref "C4") (pin "2") (pinfunction "2_2") (pintype "passive"))
      (node (ref "D3") (pin "2") (pinfunction "VOUT_2") (pintype "passive"))
      (node (ref "L1") (pin "2") (pinfunction "2_2") (pintype "passive"))
      (node (ref "L2") (pin "2") (pinfunction "2_2") (pintype "passive"))
      (node (ref "L3") (pin "2") (pinfunction "2_2") (pintype "passive"))
      (node (ref "L4") (pin "2") (pinfunction "2_2") (pintype "passive"))
      (node (ref "P1") (pin "2") (pinfunction "2_2") (pintype "passive"))
      (node (ref "R21") (pin "1") (pinfunction "1_1") (pintype "passive"))
      (node (ref "R22") (pin "1") (pinfunction "1_1") (pintype "passive"))
      (node (ref "R23") (pin "1") (pinfunction "1_1") (pintype "passive"))
      (node (ref "R24") (pin "1") (pinfunction "1_1") (pintype "passive"))
      (node (ref "R25") (pin "1") (pinfunction "1_1") (pintype "passive"))
      (node (ref "R3") (pin "1") (pinfunction "1_1") (pintype "passive"))
      (node (ref "R32") (pin "1") (pinfunction "1_1") (pintype "passive"))
      (node (ref "R4") (pin "1") (pinfunction "1_1") (pintype "passive"))
      (node (ref "R5") (pin "1") (pinfunction "1_1") (pintype "passive"))
      (node (ref "R6") (pin "1") (pinfunction "1_1") (pintype "passive"))
      (node (ref "R7") (pin "1") (pinfunction "1_1") (pintype "passive"))
    )
    (net (code "55") (name "VDDA") (class "Default")
      (node (ref "C17") (pin "1") (pinfunction "1_1") (pintype "passive"))
      (node (ref "C18") (pin "1") (pinfunction "1_1") (pintype "passive"))
      (node (ref "C19") (pin "2") (pinfunction "2_2") (pintype "passive"))
      (node (ref "C20") (pin "2") (pinfunction "2_2") (pintype "passive"))
      (node (ref "C21") (pin "1") (pinfunction "1_1") (pintype "passive"))
      (node (ref "C22") (pin "1") (pinfunction "1_1") (pintype "passive"))
      (node (ref "C23") (pin "1") (pinfunction "1_1") (pintype "passive"))
      (node (ref "C25") (pin "2") (pinfunction "2_2") (pintype "passive"))
      (node (ref "C26") (pin "2") (pinfunction "2_2") (pintype "passive"))
      (node (ref "C27") (pin "2") (pinfunction "2_2") (pintype "passive"))
      (node (ref "D1") (pin "1") (pinfunction "VDD_1") (pintype "passive"))
      (node (ref "D1") (pin "23") (pinfunction "VDD_23") (pintype "passive"))
      (node (ref "D1") (pin "28") (pinfunction "GND_28") (pintype "passive"))
      (node (ref "D1") (pin "48") (pinfunction "VDD_48") (pintype "passive"))
      (node (ref "D1") (pin "55") (pinfunction "VDDA_55") (pintype "passive"))
      (node (ref "D1") (pin "57") (pinfunction "VDDA_57") (pintype "passive"))
      (node (ref "D1") (pin "9") (pinfunction "VDD_9") (pintype "passive"))
      (node (ref "D2") (pin "2") (pinfunction "VOUT_2") (pintype "passive"))
      (node (ref "LQ1") (pin "4") (pinfunction "VDD_4") (pintype "passive"))
      (node (ref "R(REF)") (pin "1") (pinfunction "1_1") (pintype "passive"))
      (node (ref "R28") (pin "2") (pinfunction "2_2") (pintype "passive"))
      (node (ref "R30") (pin "1") (pinfunction "1_1") (pintype "passive"))
      (node (ref "Rt(1)") (pin "1") (pinfunction "1_1") (pintype "passive"))
      (node (ref "Rt(2)") (pin "1") (pinfunction "1_1") (pintype "passive"))
    )
    (net (code "56") (name "VDD_VAR1") (class "Default")
      (node (ref "C35") (pin "2") (pinfunction "2_2") (pintype "passive"))
      (node (ref "C36") (pin "2") (pinfunction "2_2") (pintype "passive"))
      (node (ref "C37") (pin "2") (pinfunction "2_2") (pintype "passive"))
      (node (ref "D4") (pin "2") (pinfunction "VOUT_2") (pintype "passive"))
      (node (ref "R34") (pin "1") (pinfunction "1_1") (pintype "passive"))
      (node (ref "X5") (pin "1") (pinfunction "0_1") (pintype "passive"))
    )
    (net (code "57") (name "VDD_VAR2") (class "Default")
      (node (ref "C40") (pin "2") (pinfunction "2_2") (pintype "passive"))
      (node (ref "C41") (pin "2") (pinfunction "2_2") (pintype "passive"))
      (node (ref "C42") (pin "2") (pinfunction "2_2") (pintype "passive"))
      (node (ref "D5") (pin "2") (pinfunction "VOUT_2") (pintype "passive"))
      (node (ref "R36") (pin "1") (pinfunction "1_1") (pintype "passive"))
      (node (ref "X5") (pin "2") (pinfunction "1_2") (pintype "passive"))
    )
    (net (code "58") (name "unconnected-(D1-RXD0-Pad51)") (class "Default")
      (node (ref "D1") (pin "51") (pinfunction "RXD0_51") (pintype "passive"))
    )
    (net (code "59") (name "unconnected-(D1-RXD1-Pad50)") (class "Default")
      (node (ref "D1") (pin "50") (pinfunction "RXD1_50") (pintype "passive"))
    )
    (net (code "60") (name "unconnected-(D1-RXD2-Pad49)") (class "Default")
      (node (ref "D1") (pin "49") (pinfunction "RXD2_49") (pintype "passive"))
    )
    (net (code "61") (name "unconnected-(D1-RXD3-Pad47)") (class "Default")
      (node (ref "D1") (pin "47") (pinfunction "RXD3_47") (pintype "passive"))
    )
    (net (code "62") (name "unconnected-(D1-RXD4-Pad46)") (class "Default")
      (node (ref "D1") (pin "46") (pinfunction "RXD4_46") (pintype "passive"))
    )
    (net (code "63") (name "unconnected-(D1-RXD5-Pad45)") (class "Default")
      (node (ref "D1") (pin "45") (pinfunction "RXD5_45") (pintype "passive"))
    )
    (net (code "64") (name "unconnected-(D1-RXD6-Pad44)") (class "Default")
      (node (ref "D1") (pin "44") (pinfunction "RXD6_44") (pintype "passive"))
    )
    (net (code "65") (name "unconnected-(D1-RXD7-Pad42)") (class "Default")
      (node (ref "D1") (pin "42") (pinfunction "RXD7_42") (pintype "passive"))
    )
    (net (code "66") (name "unconnected-(D1-RXD8-Pad40)") (class "Default")
      (node (ref "D1") (pin "40") (pinfunction "RXD8_40") (pintype "passive"))
    )
    (net (code "67") (name "unconnected-(D1-RXD9-Pad39)") (class "Default")
      (node (ref "D1") (pin "39") (pinfunction "RXD9_39") (pintype "passive"))
    )
    (net (code "68") (name "unconnected-(D1-RXD10-Pad37)") (class "Default")
      (node (ref "D1") (pin "37") (pinfunction "RXD10_37") (pintype "passive"))
    )
    (net (code "69") (name "unconnected-(D1-RXD11-Pad36)") (class "Default")
      (node (ref "D1") (pin "36") (pinfunction "RXD11_36") (pintype "passive"))
    )
    (net (code "70") (name "unconnected-(D1-RXD12-Pad35)") (class "Default")
      (node (ref "D1") (pin "35") (pinfunction "RXD12_35") (pintype "passive"))
    )
    (net (code "71") (name "unconnected-(D1-RXD13-Pad34)") (class "Default")
      (node (ref "D1") (pin "34") (pinfunction "RXD13_34") (pintype "passive"))
    )
    (net (code "72") (name "unconnected-(D1-RXD14-Pad32)") (class "Default")
      (node (ref "D1") (pin "32") (pinfunction "RXD14_32") (pintype "passive"))
    )
    (net (code "73") (name "unconnected-(D1-RXD15-Pad31)") (class "Default")
      (node (ref "D1") (pin "31") (pinfunction "RXD15_31") (pintype "passive"))
    )
    (net (code "74") (name "unconnected-(R31-Pad1)") (class "Default")
      (node (ref "R31") (pin "1") (pinfunction "1_1") (pintype "passive"))
    )
    (net (code "75") (name "unconnected-(R33-Pad1)") (class "Default")
      (node (ref "R33") (pin "1") (pinfunction "1_1") (pintype "passive"))
    )
    (net (code "76") (name "unconnected-(R35-Pad1)") (class "Default")
      (node (ref "R35") (pin "1") (pinfunction "1_1") (pintype "passive"))
    )
    (net (code "77") (name "unconnected-(R37-Pad1)") (class "Default")
      (node (ref "R37") (pin "1") (pinfunction "1_1") (pintype "passive"))
    )
    (net (code "78") (name "unconnected-(SW2---Pad4)") (class "Default")
      (node (ref "SW2") (pin "4") (pinfunction "-_4") (pintype "passive"))
    )
    (net (code "79") (name "unconnected-(SW2---Pad5)") (class "Default")
      (node (ref "SW2") (pin "5") (pinfunction "-_5") (pintype "passive"))
    )
    (net (code "80") (name "unconnected-(SW2---Pad6)") (class "Default")
      (node (ref "SW2") (pin "6") (pinfunction "-_6") (pintype "passive"))
    )
    (net (code "81") (name "unconnected-(X1-N{slash}C-Pad7)") (class "Default")
      (node (ref "X1") (pin "7") (pinfunction "N/C_7") (pintype "passive"))
    )
    (net (code "82") (name "unconnected-(X2-N{slash}C-Pad7)") (class "Default")
      (node (ref "X2") (pin "7") (pinfunction "N/C_7") (pintype "passive"))
    )
    (net (code "83") (name "unconnected-(X2-RD+-Pad13)") (class "Default")
      (node (ref "X2") (pin "13") (pinfunction "RD+_13") (pintype "passive"))
    )
    (net (code "84") (name "unconnected-(X2-RD--Pad12)") (class "Default")
      (node (ref "X2") (pin "12") (pinfunction "RD-_12") (pintype "passive"))
    )
    (net (code "85") (name "unconnected-(X2-TD+-Pad18)") (class "Default")
      (node (ref "X2") (pin "18") (pinfunction "TD+_18") (pintype "passive"))
    )
    (net (code "86") (name "unconnected-(X2-TD--Pad19)") (class "Default")
      (node (ref "X2") (pin "19") (pinfunction "TD-_19") (pintype "passive"))
    )
    (net (code "87") (name "unconnected-(X4-NC-Pad1)") (class "Default")
      (node (ref "X4") (pin "1") (pinfunction "NC_1") (pintype "passive"))
    )
    (net (code "88") (name "unconnected-(X4-NC-Pad18)") (class "Default")
      (node (ref "X4") (pin "18") (pinfunction "NC_18") (pintype "passive"))
    )
    (net (code "89") (name "unconnected-(X4-NC-Pad19)") (class "Default")
      (node (ref "X4") (pin "19") (pinfunction "NC_19") (pintype "passive"))
    )
    (net (code "90") (name "unconnected-(X4-NC-Pad37)") (class "Default")
      (node (ref "X4") (pin "37") (pinfunction "NC_37") (pintype "passive"))
    )
    (net (code "91") (name "unconnected-(X4-P0.2-Pad14)") (class "Default")
      (node (ref "X4") (pin "14") (pinfunction "P0.2_14") (pintype "passive"))
    )
    (net (code "92") (name "unconnected-(X4-P1.5-Pad26)") (class "Default")
      (node (ref "X4") (pin "26") (pinfunction "P1.5_26") (pintype "passive"))
    )
    (net (code "93") (name "unconnected-(X4-P1.6-Pad7)") (class "Default")
      (node (ref "X4") (pin "7") (pinfunction "P1.6_7") (pintype "passive"))
    )
    (net (code "94") (name "unconnected-(X4-P1.7-Pad25)") (class "Default")
      (node (ref "X4") (pin "25") (pinfunction "P1.7_25") (pintype "passive"))
    )
    (net (code "95") (name "unconnected-(X4-P2.1-Pad23)") (class "Default")
      (node (ref "X4") (pin "23") (pinfunction "P2.1_23") (pintype "passive"))
    )
    (net (code "96") (name "unconnected-(X4-P2.5-Pad21)") (class "Default")
      (node (ref "X4") (pin "21") (pinfunction "P2.5_21") (pintype "passive"))
    )
    (net (code "97") (name "unconnected-(X4-P2.7-Pad20)") (class "Default")
      (node (ref "X4") (pin "20") (pinfunction "P2.7_20") (pintype "passive"))
    )
  )
)
